# motor_controller.net
KiCad netlist of a schematic drawn in EAGLE
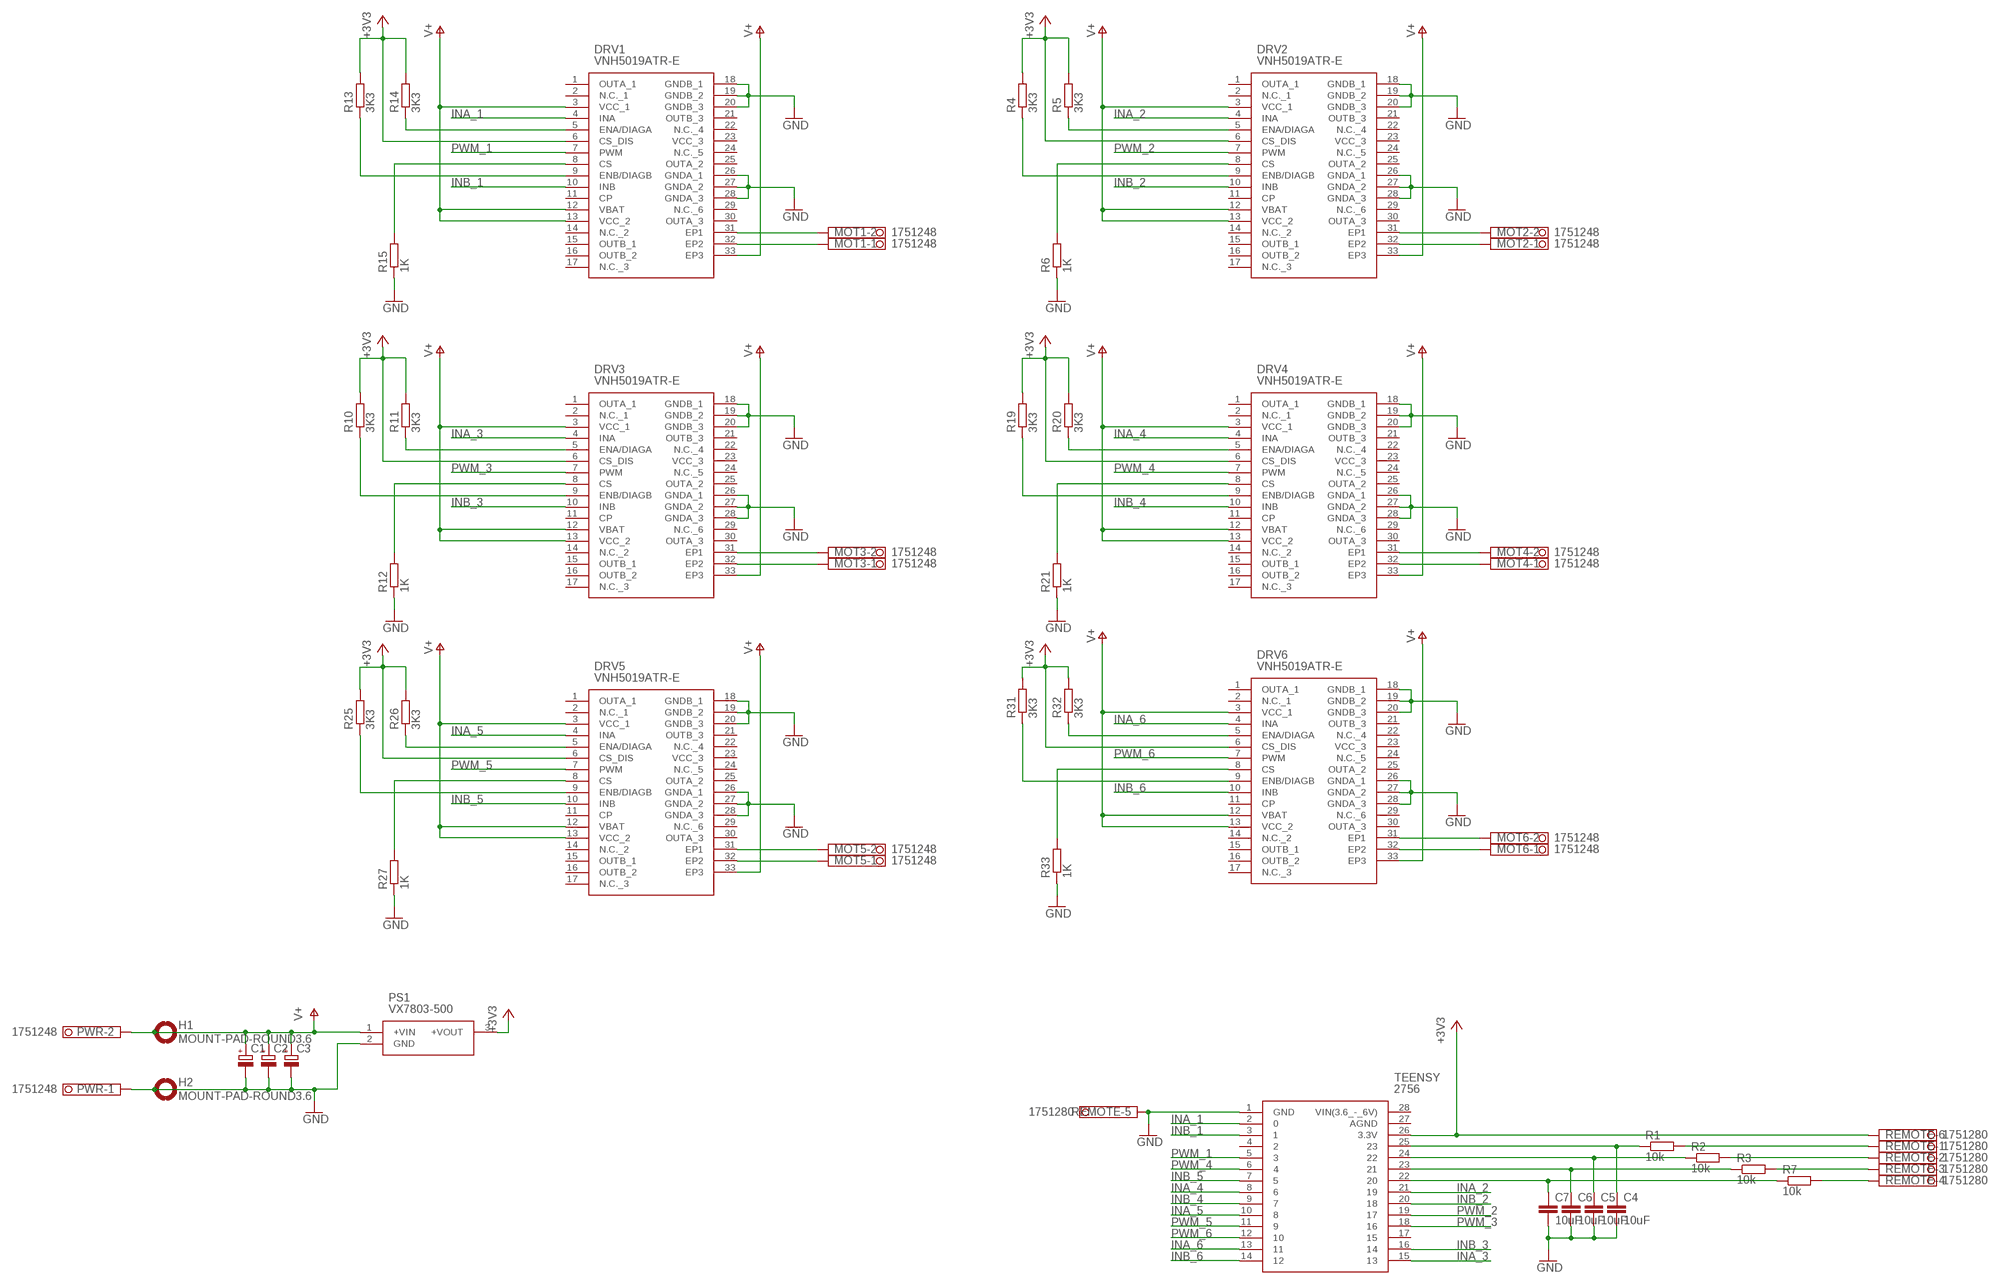
[diagram p0: schematic, sheet 1]

(export (version "E")
  (design (tool "Eeschema 10.0.6"))
  (components
    (comp (ref "C1")
      (value "CPOL-EUE10-20")
      (footprint "eagle-import:EB20D")
      (libsource (lib "eagle-import") (part "CPOL-EUE10-20"))
    )
    (comp (ref "C2")
      (value "CPOL-EUE10-20")
      (footprint "eagle-import:EB20D")
      (libsource (lib "eagle-import") (part "CPOL-EUE10-20"))
    )
    (comp (ref "C3")
      (value "CPOL-EUE10-20")
      (footprint "eagle-import:EB20D")
      (libsource (lib "eagle-import") (part "CPOL-EUE10-20"))
    )
    (comp (ref "C4")
      (value "10uF")
      (footprint "eagle-import:C0603")
      (libsource (lib "eagle-import") (part "C-EUC0603"))
    )
    (comp (ref "C5")
      (value "10uF")
      (footprint "eagle-import:C0603")
      (libsource (lib "eagle-import") (part "C-EUC0603"))
    )
    (comp (ref "C6")
      (value "10uF")
      (footprint "eagle-import:C0603")
      (libsource (lib "eagle-import") (part "C-EUC0603"))
    )
    (comp (ref "C7")
      (value "10uF")
      (footprint "eagle-import:C0603")
      (libsource (lib "eagle-import") (part "C-EUC0603"))
    )
    (comp (ref "DRV1")
      (value "VNH5019ATR-E")
      (footprint "eagle-import:VNH5019A-E_1")
      (fields
        (field (name "MOUSER_PART_NUMBER") "511-VNH5019ATR-E")
        (field (name "RS_PART_NUMBER") "1106608P")
      )
      (libsource (lib "eagle-import") (part "VNH5019ATR-E"))
    )
    (comp (ref "DRV2")
      (value "VNH5019ATR-E")
      (footprint "eagle-import:VNH5019A-E_1")
      (fields
        (field (name "MOUSER_PART_NUMBER") "511-VNH5019ATR-E")
        (field (name "RS_PART_NUMBER") "1106608P")
      )
      (libsource (lib "eagle-import") (part "VNH5019ATR-E"))
    )
    (comp (ref "DRV3")
      (value "VNH5019ATR-E")
      (footprint "eagle-import:VNH5019A-E_1")
      (fields
        (field (name "MOUSER_PART_NUMBER") "511-VNH5019ATR-E")
        (field (name "RS_PART_NUMBER") "1106608P")
      )
      (libsource (lib "eagle-import") (part "VNH5019ATR-E"))
    )
    (comp (ref "DRV4")
      (value "VNH5019ATR-E")
      (footprint "eagle-import:VNH5019A-E_1")
      (fields
        (field (name "MOUSER_PART_NUMBER") "511-VNH5019ATR-E")
        (field (name "RS_PART_NUMBER") "1106608P")
      )
      (libsource (lib "eagle-import") (part "VNH5019ATR-E"))
    )
    (comp (ref "DRV5")
      (value "VNH5019ATR-E")
      (footprint "eagle-import:VNH5019A-E_1")
      (fields
        (field (name "MOUSER_PART_NUMBER") "511-VNH5019ATR-E")
        (field (name "RS_PART_NUMBER") "1106608P")
      )
      (libsource (lib "eagle-import") (part "VNH5019ATR-E"))
    )
    (comp (ref "DRV6")
      (value "VNH5019ATR-E")
      (footprint "eagle-import:VNH5019A-E_1")
      (fields
        (field (name "MOUSER_PART_NUMBER") "511-VNH5019ATR-E")
        (field (name "RS_PART_NUMBER") "1106608P")
      )
      (libsource (lib "eagle-import") (part "VNH5019ATR-E"))
    )
    (comp (ref "H1")
      (value "MOUNT-PAD-ROUND3.6")
      (footprint "eagle-import:3,6-PAD")
      (libsource (lib "eagle-import") (part "MOUNT-PAD-ROUND3.6"))
    )
    (comp (ref "H2")
      (value "MOUNT-PAD-ROUND3.6")
      (footprint "eagle-import:3,6-PAD")
      (libsource (lib "eagle-import") (part "MOUNT-PAD-ROUND3.6"))
    )
    (comp (ref "MOT1")
      (value "1751248")
      (footprint "eagle-import:1751248")
      (libsource (lib "eagle-import") (part "1751248"))
    )
    (comp (ref "MOT2")
      (value "1751248")
      (footprint "eagle-import:1751248")
      (libsource (lib "eagle-import") (part "1751248"))
    )
    (comp (ref "MOT3")
      (value "1751248")
      (footprint "eagle-import:1751248")
      (libsource (lib "eagle-import") (part "1751248"))
    )
    (comp (ref "MOT4")
      (value "1751248")
      (footprint "eagle-import:1751248")
      (libsource (lib "eagle-import") (part "1751248"))
    )
    (comp (ref "MOT5")
      (value "1751248")
      (footprint "eagle-import:1751248")
      (libsource (lib "eagle-import") (part "1751248"))
    )
    (comp (ref "MOT6")
      (value "1751248")
      (footprint "eagle-import:1751248")
      (libsource (lib "eagle-import") (part "1751248"))
    )
    (comp (ref "PS1")
      (value "VX7803-500")
      (footprint "eagle-import:VX7805500")
      (fields
        (field (name "MANUFACTURER_PART_NUMBER") "VX7805-500")
        (field (name "MOUSER_PART_NUMBER") "490-VX7805-500")
      )
      (libsource (lib "eagle-import") (part "VX7805-500"))
    )
    (comp (ref "PWR")
      (value "1751248")
      (footprint "eagle-import:1751248")
      (libsource (lib "eagle-import") (part "1751248"))
    )
    (comp (ref "R1")
      (value "10k")
      (footprint "eagle-import:R0603")
      (libsource (lib "eagle-import") (part "R-EU_R0603"))
    )
    (comp (ref "R2")
      (value "10k")
      (footprint "eagle-import:R0603")
      (libsource (lib "eagle-import") (part "R-EU_R0603"))
    )
    (comp (ref "R3")
      (value "10k")
      (footprint "eagle-import:R0603")
      (libsource (lib "eagle-import") (part "R-EU_R0603"))
    )
    (comp (ref "R4")
      (value "3K3")
      (footprint "eagle-import:R0603")
      (libsource (lib "eagle-import") (part "R-EU_R0603"))
    )
    (comp (ref "R5")
      (value "3K3")
      (footprint "eagle-import:R0603")
      (libsource (lib "eagle-import") (part "R-EU_R0603"))
    )
    (comp (ref "R6")
      (value "1K")
      (footprint "eagle-import:R0603")
      (libsource (lib "eagle-import") (part "R-EU_R0603"))
    )
    (comp (ref "R7")
      (value "10k")
      (footprint "eagle-import:R0603")
      (libsource (lib "eagle-import") (part "R-EU_R0603"))
    )
    (comp (ref "R10")
      (value "3K3")
      (footprint "eagle-import:R0603")
      (libsource (lib "eagle-import") (part "R-EU_R0603"))
    )
    (comp (ref "R11")
      (value "3K3")
      (footprint "eagle-import:R0603")
      (libsource (lib "eagle-import") (part "R-EU_R0603"))
    )
    (comp (ref "R12")
      (value "1K")
      (footprint "eagle-import:R0603")
      (libsource (lib "eagle-import") (part "R-EU_R0603"))
    )
    (comp (ref "R13")
      (value "3K3")
      (footprint "eagle-import:R0603")
      (libsource (lib "eagle-import") (part "R-EU_R0603"))
    )
    (comp (ref "R14")
      (value "3K3")
      (footprint "eagle-import:R0603")
      (libsource (lib "eagle-import") (part "R-EU_R0603"))
    )
    (comp (ref "R15")
      (value "1K")
      (footprint "eagle-import:R0603")
      (libsource (lib "eagle-import") (part "R-EU_R0603"))
    )
    (comp (ref "R19")
      (value "3K3")
      (footprint "eagle-import:R0603")
      (libsource (lib "eagle-import") (part "R-EU_R0603"))
    )
    (comp (ref "R20")
      (value "3K3")
      (footprint "eagle-import:R0603")
      (libsource (lib "eagle-import") (part "R-EU_R0603"))
    )
    (comp (ref "R21")
      (value "1K")
      (footprint "eagle-import:R0603")
      (libsource (lib "eagle-import") (part "R-EU_R0603"))
    )
    (comp (ref "R25")
      (value "3K3")
      (footprint "eagle-import:R0603")
      (libsource (lib "eagle-import") (part "R-EU_R0603"))
    )
    (comp (ref "R26")
      (value "3K3")
      (footprint "eagle-import:R0603")
      (libsource (lib "eagle-import") (part "R-EU_R0603"))
    )
    (comp (ref "R27")
      (value "1K")
      (footprint "eagle-import:R0603")
      (libsource (lib "eagle-import") (part "R-EU_R0603"))
    )
    (comp (ref "R31")
      (value "3K3")
      (footprint "eagle-import:R0603")
      (libsource (lib "eagle-import") (part "R-EU_R0603"))
    )
    (comp (ref "R32")
      (value "3K3")
      (footprint "eagle-import:R0603")
      (libsource (lib "eagle-import") (part "R-EU_R0603"))
    )
    (comp (ref "R33")
      (value "1K")
      (footprint "eagle-import:R0603")
      (libsource (lib "eagle-import") (part "R-EU_R0603"))
    )
    (comp (ref "REMOTE")
      (value "1751280")
      (footprint "eagle-import:1751280")
      (libsource (lib "eagle-import") (part "1751280"))
    )
    (comp (ref "TEENSY")
      (value "2756")
      (footprint "eagle-import:DIP1500W100P250L3500H700Q28N")
      (fields (field (name "MOUSER_PART_NUMBER") "485-2756") (field (name "RS_PART_NUMBER") "1245510"))
      (libsource (lib "eagle-import") (part "2756"))
    )
  )
  (nets
    (net (code "1") (name "+3V3") (class "Default")
      (node (ref "DRV1") (pin "6") (pinfunction "CS_DIS_6") (pintype "bidirectional"))
      (node (ref "DRV2") (pin "6") (pinfunction "CS_DIS_6") (pintype "bidirectional"))
      (node (ref "DRV3") (pin "6") (pinfunction "CS_DIS_6") (pintype "bidirectional"))
      (node (ref "DRV4") (pin "6") (pinfunction "CS_DIS_6") (pintype "bidirectional"))
      (node (ref "DRV5") (pin "6") (pinfunction "CS_DIS_6") (pintype "bidirectional"))
      (node (ref "DRV6") (pin "6") (pinfunction "CS_DIS_6") (pintype "bidirectional"))
      (node (ref "PS1") (pin "3") (pinfunction "+VOUT_3") (pintype "bidirectional"))
      (node (ref "R10") (pin "2") (pinfunction "2_2") (pintype "passive"))
      (node (ref "R11") (pin "2") (pinfunction "2_2") (pintype "passive"))
      (node (ref "R13") (pin "2") (pinfunction "2_2") (pintype "passive"))
      (node (ref "R14") (pin "2") (pinfunction "2_2") (pintype "passive"))
      (node (ref "R19") (pin "2") (pinfunction "2_2") (pintype "passive"))
      (node (ref "R20") (pin "2") (pinfunction "2_2") (pintype "passive"))
      (node (ref "R25") (pin "2") (pinfunction "2_2") (pintype "passive"))
      (node (ref "R26") (pin "2") (pinfunction "2_2") (pintype "passive"))
      (node (ref "R31") (pin "2") (pinfunction "2_2") (pintype "passive"))
      (node (ref "R32") (pin "2") (pinfunction "2_2") (pintype "passive"))
      (node (ref "R4") (pin "2") (pinfunction "2_2") (pintype "passive"))
      (node (ref "R5") (pin "2") (pinfunction "2_2") (pintype "passive"))
      (node (ref "REMOTE") (pin "6") (pinfunction "K_6") (pintype "passive"))
      (node (ref "TEENSY") (pin "26") (pinfunction "3.3V_26") (pintype "output"))
    )
    (net (code "2") (name "/AGND") (class "Default")
      (node (ref "TEENSY") (pin "27") (pinfunction "AGND_27") (pintype "power_in"))
    )
    (net (code "3") (name "/INA_1") (class "Default")
      (node (ref "DRV1") (pin "4") (pinfunction "INA_4") (pintype "bidirectional"))
      (node (ref "TEENSY") (pin "2") (pinfunction "0_2") (pintype "input"))
    )
    (net (code "4") (name "/INA_2") (class "Default")
      (node (ref "DRV2") (pin "4") (pinfunction "INA_4") (pintype "bidirectional"))
      (node (ref "TEENSY") (pin "21") (pinfunction "19_21") (pintype "bidirectional"))
    )
    (net (code "5") (name "/INA_3") (class "Default")
      (node (ref "DRV3") (pin "4") (pinfunction "INA_4") (pintype "bidirectional"))
      (node (ref "TEENSY") (pin "15") (pinfunction "13_15") (pintype "input"))
    )
    (net (code "6") (name "/INA_4") (class "Default")
      (node (ref "DRV4") (pin "4") (pinfunction "INA_4") (pintype "bidirectional"))
      (node (ref "TEENSY") (pin "8") (pinfunction "6_8") (pintype "bidirectional"))
    )
    (net (code "7") (name "/INA_5") (class "Default")
      (node (ref "DRV5") (pin "4") (pinfunction "INA_4") (pintype "bidirectional"))
      (node (ref "TEENSY") (pin "10") (pinfunction "8_10") (pintype "output"))
    )
    (net (code "8") (name "/INA_6") (class "Default")
      (node (ref "DRV6") (pin "4") (pinfunction "INA_4") (pintype "bidirectional"))
      (node (ref "TEENSY") (pin "13") (pinfunction "11_13") (pintype "bidirectional"))
    )
    (net (code "9") (name "/INB_1") (class "Default")
      (node (ref "DRV1") (pin "10") (pinfunction "INB_10") (pintype "bidirectional"))
      (node (ref "TEENSY") (pin "3") (pinfunction "1_3") (pintype "output"))
    )
    (net (code "10") (name "/INB_2") (class "Default")
      (node (ref "DRV2") (pin "10") (pinfunction "INB_10") (pintype "bidirectional"))
      (node (ref "TEENSY") (pin "20") (pinfunction "18_20") (pintype "bidirectional"))
    )
    (net (code "11") (name "/INB_3") (class "Default")
      (node (ref "DRV3") (pin "10") (pinfunction "INB_10") (pintype "bidirectional"))
      (node (ref "TEENSY") (pin "16") (pinfunction "14_16") (pintype "bidirectional"))
    )
    (net (code "12") (name "/INB_4") (class "Default")
      (node (ref "DRV4") (pin "10") (pinfunction "INB_10") (pintype "bidirectional"))
      (node (ref "TEENSY") (pin "9") (pinfunction "7_9") (pintype "input"))
    )
    (net (code "13") (name "/INB_5") (class "Default")
      (node (ref "DRV5") (pin "10") (pinfunction "INB_10") (pintype "bidirectional"))
      (node (ref "TEENSY") (pin "7") (pinfunction "5_7") (pintype "bidirectional"))
    )
    (net (code "14") (name "/INB_6") (class "Default")
      (node (ref "DRV6") (pin "10") (pinfunction "INB_10") (pintype "bidirectional"))
      (node (ref "TEENSY") (pin "14") (pinfunction "12_14") (pintype "bidirectional"))
    )
    (net (code "15") (name "/PWM_1") (class "Default")
      (node (ref "DRV1") (pin "7") (pinfunction "PWM_7") (pintype "bidirectional"))
      (node (ref "TEENSY") (pin "5") (pinfunction "3_5") (pintype "bidirectional"))
    )
    (net (code "16") (name "/PWM_2") (class "Default")
      (node (ref "DRV2") (pin "7") (pinfunction "PWM_7") (pintype "bidirectional"))
      (node (ref "TEENSY") (pin "19") (pinfunction "17_19") (pintype "bidirectional"))
    )
    (net (code "17") (name "/PWM_3") (class "Default")
      (node (ref "DRV3") (pin "7") (pinfunction "PWM_7") (pintype "bidirectional"))
      (node (ref "TEENSY") (pin "18") (pinfunction "16_18") (pintype "bidirectional"))
    )
    (net (code "18") (name "/PWM_4") (class "Default")
      (node (ref "DRV4") (pin "7") (pinfunction "PWM_7") (pintype "bidirectional"))
      (node (ref "TEENSY") (pin "6") (pinfunction "4_6") (pintype "bidirectional"))
    )
    (net (code "19") (name "/PWM_5") (class "Default")
      (node (ref "DRV5") (pin "7") (pinfunction "PWM_7") (pintype "bidirectional"))
      (node (ref "TEENSY") (pin "11") (pinfunction "9_11") (pintype "input"))
    )
    (net (code "20") (name "/PWM_6") (class "Default")
      (node (ref "DRV6") (pin "7") (pinfunction "PWM_7") (pintype "bidirectional"))
      (node (ref "TEENSY") (pin "12") (pinfunction "10_12") (pintype "output"))
    )
    (net (code "21") (name "/VIN(3.6_-_6V)") (class "Default")
      (node (ref "TEENSY") (pin "28") (pinfunction "VIN(3.6_-_6V)_28") (pintype "power_in"))
    )
    (net (code "22") (name "GND") (class "Default")
      (node (ref "C1") (pin "-") (pinfunction "-_-") (pintype "passive"))
      (node (ref "C2") (pin "-") (pinfunction "-_-") (pintype "passive"))
      (node (ref "C3") (pin "-") (pinfunction "-_-") (pintype "passive"))
      (node (ref "C4") (pin "2") (pinfunction "2_2") (pintype "passive"))
      (node (ref "C5") (pin "2") (pinfunction "2_2") (pintype "passive"))
      (node (ref "C6") (pin "2") (pinfunction "2_2") (pintype "passive"))
      (node (ref "C7") (pin "2") (pinfunction "2_2") (pintype "passive"))
      (node (ref "DRV1") (pin "18") (pinfunction "GNDB_1_18") (pintype "bidirectional"))
      (node (ref "DRV1") (pin "19") (pinfunction "GNDB_2_19") (pintype "bidirectional"))
      (node (ref "DRV1") (pin "20") (pinfunction "GNDB_3_20") (pintype "bidirectional"))
      (node (ref "DRV1") (pin "26") (pinfunction "GNDA_1_26") (pintype "bidirectional"))
      (node (ref "DRV1") (pin "27") (pinfunction "GNDA_2_27") (pintype "bidirectional"))
      (node (ref "DRV1") (pin "28") (pinfunction "GNDA_3_28") (pintype "bidirectional"))
      (node (ref "DRV2") (pin "18") (pinfunction "GNDB_1_18") (pintype "bidirectional"))
      (node (ref "DRV2") (pin "19") (pinfunction "GNDB_2_19") (pintype "bidirectional"))
      (node (ref "DRV2") (pin "20") (pinfunction "GNDB_3_20") (pintype "bidirectional"))
      (node (ref "DRV2") (pin "26") (pinfunction "GNDA_1_26") (pintype "bidirectional"))
      (node (ref "DRV2") (pin "27") (pinfunction "GNDA_2_27") (pintype "bidirectional"))
      (node (ref "DRV2") (pin "28") (pinfunction "GNDA_3_28") (pintype "bidirectional"))
      (node (ref "DRV3") (pin "18") (pinfunction "GNDB_1_18") (pintype "bidirectional"))
      (node (ref "DRV3") (pin "19") (pinfunction "GNDB_2_19") (pintype "bidirectional"))
      (node (ref "DRV3") (pin "20") (pinfunction "GNDB_3_20") (pintype "bidirectional"))
      (node (ref "DRV3") (pin "26") (pinfunction "GNDA_1_26") (pintype "bidirectional"))
      (node (ref "DRV3") (pin "27") (pinfunction "GNDA_2_27") (pintype "bidirectional"))
      (node (ref "DRV3") (pin "28") (pinfunction "GNDA_3_28") (pintype "bidirectional"))
      (node (ref "DRV4") (pin "18") (pinfunction "GNDB_1_18") (pintype "bidirectional"))
      (node (ref "DRV4") (pin "19") (pinfunction "GNDB_2_19") (pintype "bidirectional"))
      (node (ref "DRV4") (pin "20") (pinfunction "GNDB_3_20") (pintype "bidirectional"))
      (node (ref "DRV4") (pin "26") (pinfunction "GNDA_1_26") (pintype "bidirectional"))
      (node (ref "DRV4") (pin "27") (pinfunction "GNDA_2_27") (pintype "bidirectional"))
      (node (ref "DRV4") (pin "28") (pinfunction "GNDA_3_28") (pintype "bidirectional"))
      (node (ref "DRV5") (pin "18") (pinfunction "GNDB_1_18") (pintype "bidirectional"))
      (node (ref "DRV5") (pin "19") (pinfunction "GNDB_2_19") (pintype "bidirectional"))
      (node (ref "DRV5") (pin "20") (pinfunction "GNDB_3_20") (pintype "bidirectional"))
      (node (ref "DRV5") (pin "26") (pinfunction "GNDA_1_26") (pintype "bidirectional"))
      (node (ref "DRV5") (pin "27") (pinfunction "GNDA_2_27") (pintype "bidirectional"))
      (node (ref "DRV5") (pin "28") (pinfunction "GNDA_3_28") (pintype "bidirectional"))
      (node (ref "DRV6") (pin "18") (pinfunction "GNDB_1_18") (pintype "bidirectional"))
      (node (ref "DRV6") (pin "19") (pinfunction "GNDB_2_19") (pintype "bidirectional"))
      (node (ref "DRV6") (pin "20") (pinfunction "GNDB_3_20") (pintype "bidirectional"))
      (node (ref "DRV6") (pin "26") (pinfunction "GNDA_1_26") (pintype "bidirectional"))
      (node (ref "DRV6") (pin "27") (pinfunction "GNDA_2_27") (pintype "bidirectional"))
      (node (ref "DRV6") (pin "28") (pinfunction "GNDA_3_28") (pintype "bidirectional"))
      (node (ref "H2") (pin "B3,6") (pinfunction "MOUNT_B3,6") (pintype "passive"))
      (node (ref "PS1") (pin "2") (pinfunction "GND_2") (pintype "bidirectional"))
      (node (ref "PWR") (pin "1") (pinfunction "K_1") (pintype "passive"))
      (node (ref "R12") (pin "1") (pinfunction "1_1") (pintype "passive"))
      (node (ref "R15") (pin "1") (pinfunction "1_1") (pintype "passive"))
      (node (ref "R21") (pin "1") (pinfunction "1_1") (pintype "passive"))
      (node (ref "R27") (pin "1") (pinfunction "1_1") (pintype "passive"))
      (node (ref "R33") (pin "1") (pinfunction "1_1") (pintype "passive"))
      (node (ref "R6") (pin "1") (pinfunction "1_1") (pintype "passive"))
      (node (ref "REMOTE") (pin "5") (pinfunction "K_5") (pintype "passive"))
      (node (ref "TEENSY") (pin "1") (pinfunction "GND_1") (pintype "power_in"))
    )
    (net (code "23") (name "Net-(DRV1-CS)") (class "Default")
      (node (ref "DRV1") (pin "8") (pinfunction "CS_8") (pintype "bidirectional"))
      (node (ref "R15") (pin "2") (pinfunction "2_2") (pintype "passive"))
    )
    (net (code "24") (name "Net-(DRV1-ENA{slash}DIAGA)") (class "Default")
      (node (ref "DRV1") (pin "5") (pinfunction "ENA/DIAGA_5") (pintype "bidirectional"))
      (node (ref "R14") (pin "1") (pinfunction "1_1") (pintype "passive"))
    )
    (net (code "25") (name "Net-(DRV1-ENB{slash}DIAGB)") (class "Default")
      (node (ref "DRV1") (pin "9") (pinfunction "ENB/DIAGB_9") (pintype "bidirectional"))
      (node (ref "R13") (pin "1") (pinfunction "1_1") (pintype "passive"))
    )
    (net (code "26") (name "Net-(DRV1-EP1)") (class "Default")
      (node (ref "DRV1") (pin "31") (pinfunction "EP1_31") (pintype "bidirectional"))
      (node (ref "MOT1") (pin "2") (pinfunction "K_2") (pintype "passive"))
    )
    (net (code "27") (name "Net-(DRV1-EP2)") (class "Default")
      (node (ref "DRV1") (pin "32") (pinfunction "EP2_32") (pintype "bidirectional"))
      (node (ref "MOT1") (pin "1") (pinfunction "K_1") (pintype "passive"))
    )
    (net (code "28") (name "Net-(DRV2-CS)") (class "Default")
      (node (ref "DRV2") (pin "8") (pinfunction "CS_8") (pintype "bidirectional"))
      (node (ref "R6") (pin "2") (pinfunction "2_2") (pintype "passive"))
    )
    (net (code "29") (name "Net-(DRV2-ENA{slash}DIAGA)") (class "Default")
      (node (ref "DRV2") (pin "5") (pinfunction "ENA/DIAGA_5") (pintype "bidirectional"))
      (node (ref "R5") (pin "1") (pinfunction "1_1") (pintype "passive"))
    )
    (net (code "30") (name "Net-(DRV2-ENB{slash}DIAGB)") (class "Default")
      (node (ref "DRV2") (pin "9") (pinfunction "ENB/DIAGB_9") (pintype "bidirectional"))
      (node (ref "R4") (pin "1") (pinfunction "1_1") (pintype "passive"))
    )
    (net (code "31") (name "Net-(DRV2-EP1)") (class "Default")
      (node (ref "DRV2") (pin "31") (pinfunction "EP1_31") (pintype "bidirectional"))
      (node (ref "MOT2") (pin "2") (pinfunction "K_2") (pintype "passive"))
    )
    (net (code "32") (name "Net-(DRV2-EP2)") (class "Default")
      (node (ref "DRV2") (pin "32") (pinfunction "EP2_32") (pintype "bidirectional"))
      (node (ref "MOT2") (pin "1") (pinfunction "K_1") (pintype "passive"))
    )
    (net (code "33") (name "Net-(DRV3-CS)") (class "Default")
      (node (ref "DRV3") (pin "8") (pinfunction "CS_8") (pintype "bidirectional"))
      (node (ref "R12") (pin "2") (pinfunction "2_2") (pintype "passive"))
    )
    (net (code "34") (name "Net-(DRV3-ENA{slash}DIAGA)") (class "Default")
      (node (ref "DRV3") (pin "5") (pinfunction "ENA/DIAGA_5") (pintype "bidirectional"))
      (node (ref "R11") (pin "1") (pinfunction "1_1") (pintype "passive"))
    )
    (net (code "35") (name "Net-(DRV3-ENB{slash}DIAGB)") (class "Default")
      (node (ref "DRV3") (pin "9") (pinfunction "ENB/DIAGB_9") (pintype "bidirectional"))
      (node (ref "R10") (pin "1") (pinfunction "1_1") (pintype "passive"))
    )
    (net (code "36") (name "Net-(DRV3-EP1)") (class "Default")
      (node (ref "DRV3") (pin "31") (pinfunction "EP1_31") (pintype "bidirectional"))
      (node (ref "MOT3") (pin "2") (pinfunction "K_2") (pintype "passive"))
    )
    (net (code "37") (name "Net-(DRV3-EP2)") (class "Default")
      (node (ref "DRV3") (pin "32") (pinfunction "EP2_32") (pintype "bidirectional"))
      (node (ref "MOT3") (pin "1") (pinfunction "K_1") (pintype "passive"))
    )
    (net (code "38") (name "Net-(DRV4-CS)") (class "Default")
      (node (ref "DRV4") (pin "8") (pinfunction "CS_8") (pintype "bidirectional"))
      (node (ref "R21") (pin "2") (pinfunction "2_2") (pintype "passive"))
    )
    (net (code "39") (name "Net-(DRV4-ENA{slash}DIAGA)") (class "Default")
      (node (ref "DRV4") (pin "5") (pinfunction "ENA/DIAGA_5") (pintype "bidirectional"))
      (node (ref "R20") (pin "1") (pinfunction "1_1") (pintype "passive"))
    )
    (net (code "40") (name "Net-(DRV4-ENB{slash}DIAGB)") (class "Default")
      (node (ref "DRV4") (pin "9") (pinfunction "ENB/DIAGB_9") (pintype "bidirectional"))
      (node (ref "R19") (pin "1") (pinfunction "1_1") (pintype "passive"))
    )
    (net (code "41") (name "Net-(DRV4-EP1)") (class "Default")
      (node (ref "DRV4") (pin "31") (pinfunction "EP1_31") (pintype "bidirectional"))
      (node (ref "MOT4") (pin "2") (pinfunction "K_2") (pintype "passive"))
    )
    (net (code "42") (name "Net-(DRV4-EP2)") (class "Default")
      (node (ref "DRV4") (pin "32") (pinfunction "EP2_32") (pintype "bidirectional"))
      (node (ref "MOT4") (pin "1") (pinfunction "K_1") (pintype "passive"))
    )
    (net (code "43") (name "Net-(DRV5-CS)") (class "Default")
      (node (ref "DRV5") (pin "8") (pinfunction "CS_8") (pintype "bidirectional"))
      (node (ref "R27") (pin "2") (pinfunction "2_2") (pintype "passive"))
    )
    (net (code "44") (name "Net-(DRV5-ENA{slash}DIAGA)") (class "Default")
      (node (ref "DRV5") (pin "5") (pinfunction "ENA/DIAGA_5") (pintype "bidirectional"))
      (node (ref "R26") (pin "1") (pinfunction "1_1") (pintype "passive"))
    )
    (net (code "45") (name "Net-(DRV5-ENB{slash}DIAGB)") (class "Default")
      (node (ref "DRV5") (pin "9") (pinfunction "ENB/DIAGB_9") (pintype "bidirectional"))
      (node (ref "R25") (pin "1") (pinfunction "1_1") (pintype "passive"))
    )
    (net (code "46") (name "Net-(DRV5-EP1)") (class "Default")
      (node (ref "DRV5") (pin "31") (pinfunction "EP1_31") (pintype "bidirectional"))
      (node (ref "MOT5") (pin "2") (pinfunction "K_2") (pintype "passive"))
    )
    (net (code "47") (name "Net-(DRV5-EP2)") (class "Default")
      (node (ref "DRV5") (pin "32") (pinfunction "EP2_32") (pintype "bidirectional"))
      (node (ref "MOT5") (pin "1") (pinfunction "K_1") (pintype "passive"))
    )
    (net (code "48") (name "Net-(DRV6-CS)") (class "Default")
      (node (ref "DRV6") (pin "8") (pinfunction "CS_8") (pintype "bidirectional"))
      (node (ref "R33") (pin "2") (pinfunction "2_2") (pintype "passive"))
    )
    (net (code "49") (name "Net-(DRV6-ENA{slash}DIAGA)") (class "Default")
      (node (ref "DRV6") (pin "5") (pinfunction "ENA/DIAGA_5") (pintype "bidirectional"))
      (node (ref "R32") (pin "1") (pinfunction "1_1") (pintype "passive"))
    )
    (net (code "50") (name "Net-(DRV6-ENB{slash}DIAGB)") (class "Default")
      (node (ref "DRV6") (pin "9") (pinfunction "ENB/DIAGB_9") (pintype "bidirectional"))
      (node (ref "R31") (pin "1") (pinfunction "1_1") (pintype "passive"))
    )
    (net (code "51") (name "Net-(DRV6-EP1)") (class "Default")
      (node (ref "DRV6") (pin "31") (pinfunction "EP1_31") (pintype "bidirectional"))
      (node (ref "MOT6") (pin "2") (pinfunction "K_2") (pintype "passive"))
    )
    (net (code "52") (name "Net-(DRV6-EP2)") (class "Default")
      (node (ref "DRV6") (pin "32") (pinfunction "EP2_32") (pintype "bidirectional"))
      (node (ref "MOT6") (pin "1") (pinfunction "K_1") (pintype "passive"))
    )
    (net (code "53") (name "Net-(REMOTEA-K)") (class "Default")
      (node (ref "R1") (pin "2") (pinfunction "2_2") (pintype "passive"))
      (node (ref "REMOTE") (pin "1") (pinfunction "K_1") (pintype "passive"))
    )
    (net (code "54") (name "Net-(REMOTEB-K)") (class "Default")
      (node (ref "R2") (pin "2") (pinfunction "2_2") (pintype "passive"))
      (node (ref "REMOTE") (pin "2") (pinfunction "K_2") (pintype "passive"))
    )
    (net (code "55") (name "Net-(REMOTEC-K)") (class "Default")
      (node (ref "R3") (pin "2") (pinfunction "2_2") (pintype "passive"))
      (node (ref "REMOTE") (pin "3") (pinfunction "K_3") (pintype "passive"))
    )
    (net (code "56") (name "Net-(REMOTED-K)") (class "Default")
      (node (ref "R7") (pin "2") (pinfunction "2_2") (pintype "passive"))
      (node (ref "REMOTE") (pin "4") (pinfunction "K_4") (pintype "passive"))
    )
    (net (code "57") (name "Net-(TEENSY-20)") (class "Default")
      (node (ref "C7") (pin "1") (pinfunction "1_1") (pintype "passive"))
      (node (ref "R7") (pin "1") (pinfunction "1_1") (pintype "passive"))
      (node (ref "TEENSY") (pin "22") (pinfunction "20_22") (pintype "bidirectional"))
    )
    (net (code "58") (name "Net-(TEENSY-21)") (class "Default")
      (node (ref "C6") (pin "1") (pinfunction "1_1") (pintype "passive"))
      (node (ref "R3") (pin "1") (pinfunction "1_1") (pintype "passive"))
      (node (ref "TEENSY") (pin "23") (pinfunction "21_23") (pintype "bidirectional"))
    )
    (net (code "59") (name "Net-(TEENSY-22)") (class "Default")
      (node (ref "C5") (pin "1") (pinfunction "1_1") (pintype "passive"))
      (node (ref "R2") (pin "1") (pinfunction "1_1") (pintype "passive"))
      (node (ref "TEENSY") (pin "24") (pinfunction "22_24") (pintype "bidirectional"))
    )
    (net (code "60") (name "Net-(TEENSY-23)") (class "Default")
      (node (ref "C4") (pin "1") (pinfunction "1_1") (pintype "passive"))
      (node (ref "R1") (pin "1") (pinfunction "1_1") (pintype "passive"))
      (node (ref "TEENSY") (pin "25") (pinfunction "23_25") (pintype "bidirectional"))
    )
    (net (code "61") (name "V+") (class "Default")
      (node (ref "C1") (pin "+") (pinfunction "+_+") (pintype "passive"))
      (node (ref "C2") (pin "+") (pinfunction "+_+") (pintype "passive"))
      (node (ref "C3") (pin "+") (pinfunction "+_+") (pintype "passive"))
      (node (ref "DRV1") (pin "12") (pinfunction "VBAT_12") (pintype "bidirectional"))
      (node (ref "DRV1") (pin "13") (pinfunction "VCC_2_13") (pintype "bidirectional"))
      (node (ref "DRV1") (pin "3") (pinfunction "VCC_1_3") (pintype "bidirectional"))
      (node (ref "DRV1") (pin "33") (pinfunction "EP3_33") (pintype "bidirectional"))
      (node (ref "DRV2") (pin "12") (pinfunction "VBAT_12") (pintype "bidirectional"))
      (node (ref "DRV2") (pin "13") (pinfunction "VCC_2_13") (pintype "bidirectional"))
      (node (ref "DRV2") (pin "3") (pinfunction "VCC_1_3") (pintype "bidirectional"))
      (node (ref "DRV2") (pin "33") (pinfunction "EP3_33") (pintype "bidirectional"))
      (node (ref "DRV3") (pin "12") (pinfunction "VBAT_12") (pintype "bidirectional"))
      (node (ref "DRV3") (pin "13") (pinfunction "VCC_2_13") (pintype "bidirectional"))
      (node (ref "DRV3") (pin "3") (pinfunction "VCC_1_3") (pintype "bidirectional"))
      (node (ref "DRV3") (pin "33") (pinfunction "EP3_33") (pintype "bidirectional"))
      (node (ref "DRV4") (pin "12") (pinfunction "VBAT_12") (pintype "bidirectional"))
      (node (ref "DRV4") (pin "13") (pinfunction "VCC_2_13") (pintype "bidirectional"))
      (node (ref "DRV4") (pin "3") (pinfunction "VCC_1_3") (pintype "bidirectional"))
      (node (ref "DRV4") (pin "33") (pinfunction "EP3_33") (pintype "bidirectional"))
      (node (ref "DRV5") (pin "12") (pinfunction "VBAT_12") (pintype "bidirectional"))
      (node (ref "DRV5") (pin "13") (pinfunction "VCC_2_13") (pintype "bidirectional"))
      (node (ref "DRV5") (pin "3") (pinfunction "VCC_1_3") (pintype "bidirectional"))
      (node (ref "DRV5") (pin "33") (pinfunction "EP3_33") (pintype "bidirectional"))
      (node (ref "DRV6") (pin "12") (pinfunction "VBAT_12") (pintype "bidirectional"))
      (node (ref "DRV6") (pin "13") (pinfunction "VCC_2_13") (pintype "bidirectional"))
      (node (ref "DRV6") (pin "3") (pinfunction "VCC_1_3") (pintype "bidirectional"))
      (node (ref "DRV6") (pin "33") (pinfunction "EP3_33") (pintype "bidirectional"))
      (node (ref "H1") (pin "B3,6") (pinfunction "MOUNT_B3,6") (pintype "passive"))
      (node (ref "PS1") (pin "1") (pinfunction "+VIN_1") (pintype "bidirectional"))
      (node (ref "PWR") (pin "2") (pinfunction "K_2") (pintype "passive"))
    )
    (net (code "62") (name "unconnected-(DRV1-CP-Pad11)") (class "Default")
      (node (ref "DRV1") (pin "11") (pinfunction "CP_11") (pintype "bidirectional"))
    )
    (net (code "63") (name "unconnected-(DRV1-N.C._1-Pad2)") (class "Default")
      (node (ref "DRV1") (pin "2") (pinfunction "N.C._1_2") (pintype "bidirectional"))
    )
    (net (code "64") (name "unconnected-(DRV1-N.C._2-Pad14)") (class "Default")
      (node (ref "DRV1") (pin "14") (pinfunction "N.C._2_14") (pintype "bidirectional"))
    )
    (net (code "65") (name "unconnected-(DRV1-N.C._3-Pad17)") (class "Default")
      (node (ref "DRV1") (pin "17") (pinfunction "N.C._3_17") (pintype "bidirectional"))
    )
    (net (code "66") (name "unconnected-(DRV1-N.C._4-Pad22)") (class "Default")
      (node (ref "DRV1") (pin "22") (pinfunction "N.C._4_22") (pintype "bidirectional"))
    )
    (net (code "67") (name "unconnected-(DRV1-N.C._5-Pad24)") (class "Default")
      (node (ref "DRV1") (pin "24") (pinfunction "N.C._5_24") (pintype "bidirectional"))
    )
    (net (code "68") (name "unconnected-(DRV1-N.C._6-Pad29)") (class "Default")
      (node (ref "DRV1") (pin "29") (pinfunction "N.C._6_29") (pintype "bidirectional"))
    )
    (net (code "69") (name "unconnected-(DRV1-OUTA_1-Pad1)") (class "Default")
      (node (ref "DRV1") (pin "1") (pinfunction "OUTA_1_1") (pintype "bidirectional"))
    )
    (net (code "70") (name "unconnected-(DRV1-OUTA_2-Pad25)") (class "Default")
      (node (ref "DRV1") (pin "25") (pinfunction "OUTA_2_25") (pintype "bidirectional"))
    )
    (net (code "71") (name "unconnected-(DRV1-OUTA_3-Pad30)") (class "Default")
      (node (ref "DRV1") (pin "30") (pinfunction "OUTA_3_30") (pintype "bidirectional"))
    )
    (net (code "72") (name "unconnected-(DRV1-OUTB_1-Pad15)") (class "Default")
      (node (ref "DRV1") (pin "15") (pinfunction "OUTB_1_15") (pintype "bidirectional"))
    )
    (net (code "73") (name "unconnected-(DRV1-OUTB_2-Pad16)") (class "Default")
      (node (ref "DRV1") (pin "16") (pinfunction "OUTB_2_16") (pintype "bidirectional"))
    )
    (net (code "74") (name "unconnected-(DRV1-OUTB_3-Pad21)") (class "Default")
      (node (ref "DRV1") (pin "21") (pinfunction "OUTB_3_21") (pintype "bidirectional"))
    )
    (net (code "75") (name "unconnected-(DRV1-VCC_3-Pad23)") (class "Default")
      (node (ref "DRV1") (pin "23") (pinfunction "VCC_3_23") (pintype "bidirectional"))
    )
    (net (code "76") (name "unconnected-(DRV2-CP-Pad11)") (class "Default")
      (node (ref "DRV2") (pin "11") (pinfunction "CP_11") (pintype "bidirectional"))
    )
    (net (code "77") (name "unconnected-(DRV2-N.C._1-Pad2)") (class "Default")
      (node (ref "DRV2") (pin "2") (pinfunction "N.C._1_2") (pintype "bidirectional"))
    )
    (net (code "78") (name "unconnected-(DRV2-N.C._2-Pad14)") (class "Default")
      (node (ref "DRV2") (pin "14") (pinfunction "N.C._2_14") (pintype "bidirectional"))
    )
    (net (code "79") (name "unconnected-(DRV2-N.C._3-Pad17)") (class "Default")
      (node (ref "DRV2") (pin "17") (pinfunction "N.C._3_17") (pintype "bidirectional"))
    )
    (net (code "80") (name "unconnected-(DRV2-N.C._4-Pad22)") (class "Default")
      (node (ref "DRV2") (pin "22") (pinfunction "N.C._4_22") (pintype "bidirectional"))
    )
    (net (code "81") (name "unconnected-(DRV2-N.C._5-Pad24)") (class "Default")
      (node (ref "DRV2") (pin "24") (pinfunction "N.C._5_24") (pintype "bidirectional"))
    )
    (net (code "82") (name "unconnected-(DRV2-N.C._6-Pad29)") (class "Default")
      (node (ref "DRV2") (pin "29") (pinfunction "N.C._6_29") (pintype "bidirectional"))
    )
    (net (code "83") (name "unconnected-(DRV2-OUTA_1-Pad1)") (class "Default")
      (node (ref "DRV2") (pin "1") (pinfunction "OUTA_1_1") (pintype "bidirectional"))
    )
    (net (code "84") (name "unconnected-(DRV2-OUTA_2-Pad25)") (class "Default")
      (node (ref "DRV2") (pin "25") (pinfunction "OUTA_2_25") (pintype "bidirectional"))
    )
    (net (code "85") (name "unconnected-(DRV2-OUTA_3-Pad30)") (class "Default")
      (node (ref "DRV2") (pin "30") (pinfunction "OUTA_3_30") (pintype "bidirectional"))
    )
    (net (code "86") (name "unconnected-(DRV2-OUTB_1-Pad15)") (class "Default")
      (node (ref "DRV2") (pin "15") (pinfunction "OUTB_1_15") (pintype "bidirectional"))
    )
    (net (code "87") (name "unconnected-(DRV2-OUTB_2-Pad16)") (class "Default")
      (node (ref "DRV2") (pin "16") (pinfunction "OUTB_2_16") (pintype "bidirectional"))
    )
    (net (code "88") (name "unconnected-(DRV2-OUTB_3-Pad21)") (class "Default")
      (node (ref "DRV2") (pin "21") (pinfunction "OUTB_3_21") (pintype "bidirectional"))
    )
    (net (code "89") (name "unconnected-(DRV2-VCC_3-Pad23)") (class "Default")
      (node (ref "DRV2") (pin "23") (pinfunction "VCC_3_23") (pintype "bidirectional"))
    )
    (net (code "90") (name "unconnected-(DRV3-CP-Pad11)") (class "Default")
      (node (ref "DRV3") (pin "11") (pinfunction "CP_11") (pintype "bidirectional"))
    )
    (net (code "91") (name "unconnected-(DRV3-N.C._1-Pad2)") (class "Default")
      (node (ref "DRV3") (pin "2") (pinfunction "N.C._1_2") (pintype "bidirectional"))
    )
    (net (code "92") (name "unconnected-(DRV3-N.C._2-Pad14)") (class "Default")
      (node (ref "DRV3") (pin "14") (pinfunction "N.C._2_14") (pintype "bidirectional"))
    )
    (net (code "93") (name "unconnected-(DRV3-N.C._3-Pad17)") (class "Default")
      (node (ref "DRV3") (pin "17") (pinfunction "N.C._3_17") (pintype "bidirectional"))
    )
    (net (code "94") (name "unconnected-(DRV3-N.C._4-Pad22)") (class "Default")
      (node (ref "DRV3") (pin "22") (pinfunction "N.C._4_22") (pintype "bidirectional"))
    )
    (net (code "95") (name "unconnected-(DRV3-N.C._5-Pad24)") (class "Default")
      (node (ref "DRV3") (pin "24") (pinfunction "N.C._5_24") (pintype "bidirectional"))
    )
    (net (code "96") (name "unconnected-(DRV3-N.C._6-Pad29)") (class "Default")
      (node (ref "DRV3") (pin "29") (pinfunction "N.C._6_29") (pintype "bidirectional"))
    )
    (net (code "97") (name "unconnected-(DRV3-OUTA_1-Pad1)") (class "Default")
      (node (ref "DRV3") (pin "1") (pinfunction "OUTA_1_1") (pintype "bidirectional"))
    )
    (net (code "98") (name "unconnected-(DRV3-OUTA_2-Pad25)") (class "Default")
      (node (ref "DRV3") (pin "25") (pinfunction "OUTA_2_25") (pintype "bidirectional"))
    )
    (net (code "99") (name "unconnected-(DRV3-OUTA_3-Pad30)") (class "Default")
      (node (ref "DRV3") (pin "30") (pinfunction "OUTA_3_30") (pintype "bidirectional"))
    )
    (net (code "100") (name "unconnected-(DRV3-OUTB_1-Pad15)") (class "Default")
      (node (ref "DRV3") (pin "15") (pinfunction "OUTB_1_15") (pintype "bidirectional"))
    )
    (net (code "101") (name "unconnected-(DRV3-OUTB_2-Pad16)") (class "Default")
      (node (ref "DRV3") (pin "16") (pinfunction "OUTB_2_16") (pintype "bidirectional"))
    )
    (net (code "102") (name "unconnected-(DRV3-OUTB_3-Pad21)") (class "Default")
      (node (ref "DRV3") (pin "21") (pinfunction "OUTB_3_21") (pintype "bidirectional"))
    )
    (net (code "103") (name "unconnected-(DRV3-VCC_3-Pad23)") (class "Default")
      (node (ref "DRV3") (pin "23") (pinfunction "VCC_3_23") (pintype "bidirectional"))
    )
    (net (code "104") (name "unconnected-(DRV4-CP-Pad11)") (class "Default")
      (node (ref "DRV4") (pin "11") (pinfunction "CP_11") (pintype "bidirectional"))
    )
    (net (code "105") (name "unconnected-(DRV4-N.C._1-Pad2)") (class "Default")
      (node (ref "DRV4") (pin "2") (pinfunction "N.C._1_2") (pintype "bidirectional"))
    )
    (net (code "106") (name "unconnected-(DRV4-N.C._2-Pad14)") (class "Default")
      (node (ref "DRV4") (pin "14") (pinfunction "N.C._2_14") (pintype "bidirectional"))
    )
    (net (code "107") (name "unconnected-(DRV4-N.C._3-Pad17)") (class "Default")
      (node (ref "DRV4") (pin "17") (pinfunction "N.C._3_17") (pintype "bidirectional"))
    )
    (net (code "108") (name "unconnected-(DRV4-N.C._4-Pad22)") (class "Default")
      (node (ref "DRV4") (pin "22") (pinfunction "N.C._4_22") (pintype "bidirectional"))
    )
    (net (code "109") (name "unconnected-(DRV4-N.C._5-Pad24)") (class "Default")
      (node (ref "DRV4") (pin "24") (pinfunction "N.C._5_24") (pintype "bidirectional"))
    )
    (net (code "110") (name "unconnected-(DRV4-N.C._6-Pad29)") (class "Default")
      (node (ref "DRV4") (pin "29") (pinfunction "N.C._6_29") (pintype "bidirectional"))
    )
    (net (code "111") (name "unconnected-(DRV4-OUTA_1-Pad1)") (class "Default")
      (node (ref "DRV4") (pin "1") (pinfunction "OUTA_1_1") (pintype "bidirectional"))
    )
    (net (code "112") (name "unconnected-(DRV4-OUTA_2-Pad25)") (class "Default")
      (node (ref "DRV4") (pin "25") (pinfunction "OUTA_2_25") (pintype "bidirectional"))
    )
    (net (code "113") (name "unconnected-(DRV4-OUTA_3-Pad30)") (class "Default")
      (node (ref "DRV4") (pin "30") (pinfunction "OUTA_3_30") (pintype "bidirectional"))
    )
    (net (code "114") (name "unconnected-(DRV4-OUTB_1-Pad15)") (class "Default")
      (node (ref "DRV4") (pin "15") (pinfunction "OUTB_1_15") (pintype "bidirectional"))
    )
    (net (code "115") (name "unconnected-(DRV4-OUTB_2-Pad16)") (class "Default")
      (node (ref "DRV4") (pin "16") (pinfunction "OUTB_2_16") (pintype "bidirectional"))
    )
    (net (code "116") (name "unconnected-(DRV4-OUTB_3-Pad21)") (class "Default")
      (node (ref "DRV4") (pin "21") (pinfunction "OUTB_3_21") (pintype "bidirectional"))
    )
    (net (code "117") (name "unconnected-(DRV4-VCC_3-Pad23)") (class "Default")
      (node (ref "DRV4") (pin "23") (pinfunction "VCC_3_23") (pintype "bidirectional"))
    )
    (net (code "118") (name "unconnected-(DRV5-CP-Pad11)") (class "Default")
      (node (ref "DRV5") (pin "11") (pinfunction "CP_11") (pintype "bidirectional"))
    )
    (net (code "119") (name "unconnected-(DRV5-N.C._1-Pad2)") (class "Default")
      (node (ref "DRV5") (pin "2") (pinfunction "N.C._1_2") (pintype "bidirectional"))
    )
    (net (code "120") (name "unconnected-(DRV5-N.C._2-Pad14)") (class "Default")
      (node (ref "DRV5") (pin "14") (pinfunction "N.C._2_14") (pintype "bidirectional"))
    )
    (net (code "121") (name "unconnected-(DRV5-N.C._3-Pad17)") (class "Default")
      (node (ref "DRV5") (pin "17") (pinfunction "N.C._3_17") (pintype "bidirectional"))
    )
    (net (code "122") (name "unconnected-(DRV5-N.C._4-Pad22)") (class "Default")
      (node (ref "DRV5") (pin "22") (pinfunction "N.C._4_22") (pintype "bidirectional"))
    )
    (net (code "123") (name "unconnected-(DRV5-N.C._5-Pad24)") (class "Default")
      (node (ref "DRV5") (pin "24") (pinfunction "N.C._5_24") (pintype "bidirectional"))
    )
    (net (code "124") (name "unconnected-(DRV5-N.C._6-Pad29)") (class "Default")
      (node (ref "DRV5") (pin "29") (pinfunction "N.C._6_29") (pintype "bidirectional"))
    )
    (net (code "125") (name "unconnected-(DRV5-OUTA_1-Pad1)") (class "Default")
      (node (ref "DRV5") (pin "1") (pinfunction "OUTA_1_1") (pintype "bidirectional"))
    )
    (net (code "126") (name "unconnected-(DRV5-OUTA_2-Pad25)") (class "Default")
      (node (ref "DRV5") (pin "25") (pinfunction "OUTA_2_25") (pintype "bidirectional"))
    )
    (net (code "127") (name "unconnected-(DRV5-OUTA_3-Pad30)") (class "Default")
      (node (ref "DRV5") (pin "30") (pinfunction "OUTA_3_30") (pintype "bidirectional"))
    )
    (net (code "128") (name "unconnected-(DRV5-OUTB_1-Pad15)") (class "Default")
      (node (ref "DRV5") (pin "15") (pinfunction "OUTB_1_15") (pintype "bidirectional"))
    )
    (net (code "129") (name "unconnected-(DRV5-OUTB_2-Pad16)") (class "Default")
      (node (ref "DRV5") (pin "16") (pinfunction "OUTB_2_16") (pintype "bidirectional"))
    )
    (net (code "130") (name "unconnected-(DRV5-OUTB_3-Pad21)") (class "Default")
      (node (ref "DRV5") (pin "21") (pinfunction "OUTB_3_21") (pintype "bidirectional"))
    )
    (net (code "131") (name "unconnected-(DRV5-VCC_3-Pad23)") (class "Default")
      (node (ref "DRV5") (pin "23") (pinfunction "VCC_3_23") (pintype "bidirectional"))
    )
    (net (code "132") (name "unconnected-(DRV6-CP-Pad11)") (class "Default")
      (node (ref "DRV6") (pin "11") (pinfunction "CP_11") (pintype "bidirectional"))
    )
    (net (code "133") (name "unconnected-(DRV6-N.C._1-Pad2)") (class "Default")
      (node (ref "DRV6") (pin "2") (pinfunction "N.C._1_2") (pintype "bidirectional"))
    )
    (net (code "134") (name "unconnected-(DRV6-N.C._2-Pad14)") (class "Default")
      (node (ref "DRV6") (pin "14") (pinfunction "N.C._2_14") (pintype "bidirectional"))
    )
    (net (code "135") (name "unconnected-(DRV6-N.C._3-Pad17)") (class "Default")
      (node (ref "DRV6") (pin "17") (pinfunction "N.C._3_17") (pintype "bidirectional"))
    )
    (net (code "136") (name "unconnected-(DRV6-N.C._4-Pad22)") (class "Default")
      (node (ref "DRV6") (pin "22") (pinfunction "N.C._4_22") (pintype "bidirectional"))
    )
    (net (code "137") (name "unconnected-(DRV6-N.C._5-Pad24)") (class "Default")
      (node (ref "DRV6") (pin "24") (pinfunction "N.C._5_24") (pintype "bidirectional"))
    )
    (net (code "138") (name "unconnected-(DRV6-N.C._6-Pad29)") (class "Default")
      (node (ref "DRV6") (pin "29") (pinfunction "N.C._6_29") (pintype "bidirectional"))
    )
    (net (code "139") (name "unconnected-(DRV6-OUTA_1-Pad1)") (class "Default")
      (node (ref "DRV6") (pin "1") (pinfunction "OUTA_1_1") (pintype "bidirectional"))
    )
    (net (code "140") (name "unconnected-(DRV6-OUTA_2-Pad25)") (class "Default")
      (node (ref "DRV6") (pin "25") (pinfunction "OUTA_2_25") (pintype "bidirectional"))
    )
    (net (code "141") (name "unconnected-(DRV6-OUTA_3-Pad30)") (class "Default")
      (node (ref "DRV6") (pin "30") (pinfunction "OUTA_3_30") (pintype "bidirectional"))
    )
    (net (code "142") (name "unconnected-(DRV6-OUTB_1-Pad15)") (class "Default")
      (node (ref "DRV6") (pin "15") (pinfunction "OUTB_1_15") (pintype "bidirectional"))
    )
    (net (code "143") (name "unconnected-(DRV6-OUTB_2-Pad16)") (class "Default")
      (node (ref "DRV6") (pin "16") (pinfunction "OUTB_2_16") (pintype "bidirectional"))
    )
    (net (code "144") (name "unconnected-(DRV6-OUTB_3-Pad21)") (class "Default")
      (node (ref "DRV6") (pin "21") (pinfunction "OUTB_3_21") (pintype "bidirectional"))
    )
    (net (code "145") (name "unconnected-(DRV6-VCC_3-Pad23)") (class "Default")
      (node (ref "DRV6") (pin "23") (pinfunction "VCC_3_23") (pintype "bidirectional"))
    )
    (net (code "146") (name "unconnected-(TEENSY-2-Pad4)") (class "Default")
      (node (ref "TEENSY") (pin "4") (pinfunction "2_4") (pintype "bidirectional"))
    )
    (net (code "147") (name "unconnected-(TEENSY-15-Pad17)") (class "Default")
      (node (ref "TEENSY") (pin "17") (pinfunction "15_17") (pintype "bidirectional"))
    )
  )
)
